# Sheet2.net
KiCad netlist of a schematic drawn in Altium Designer
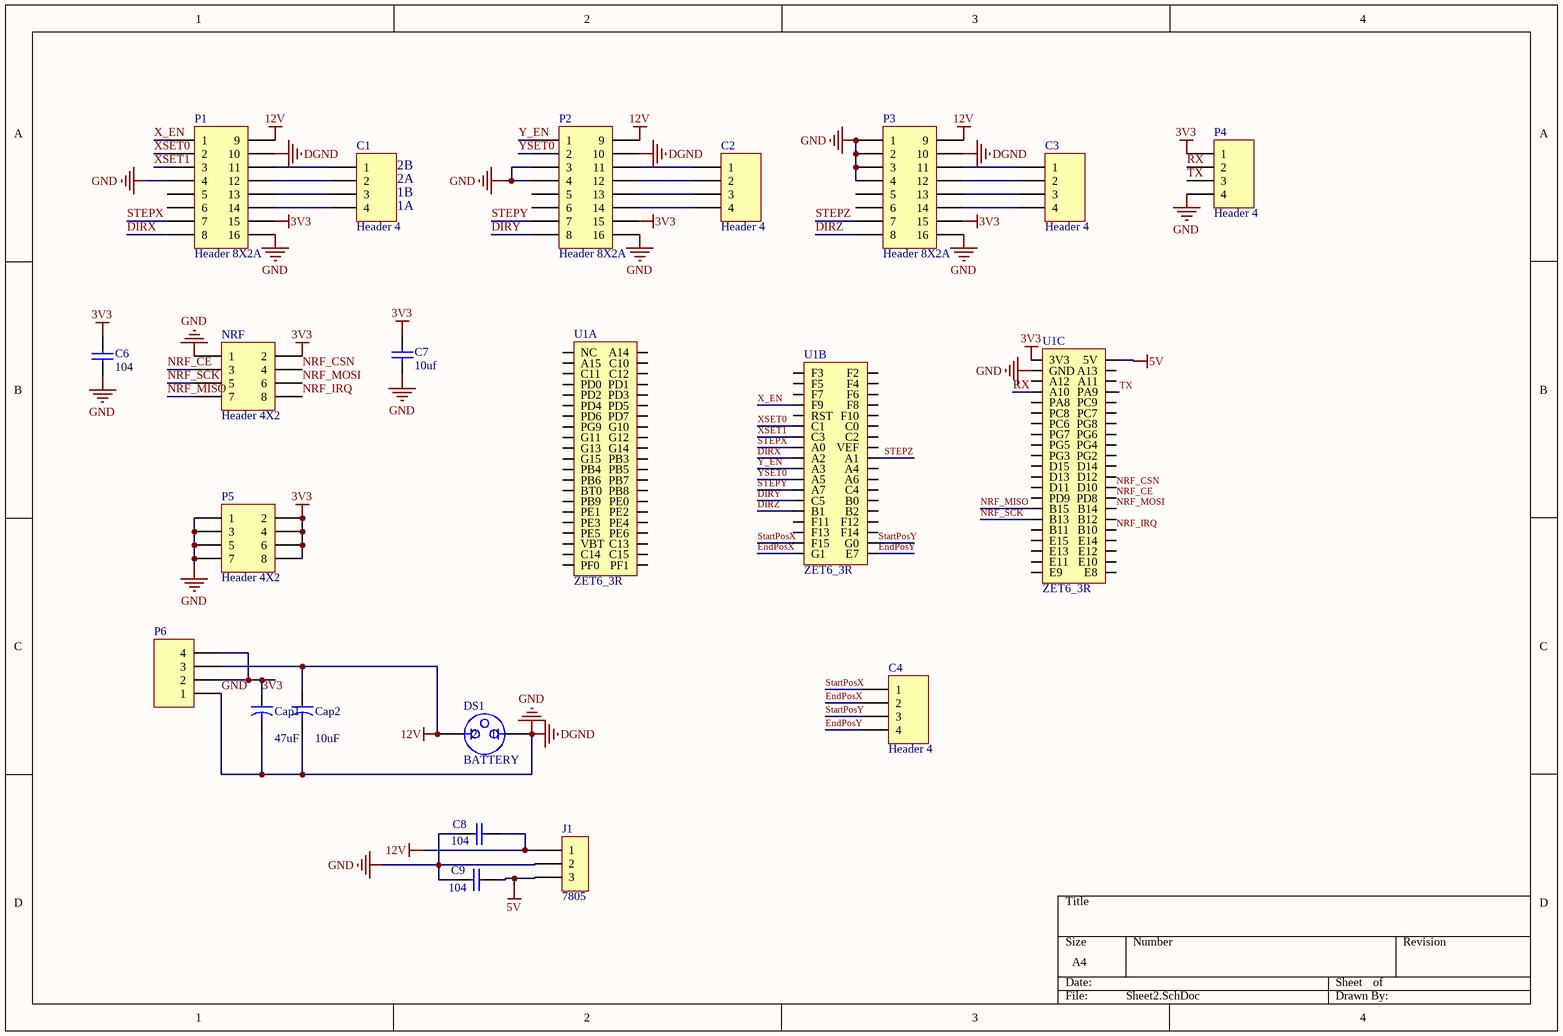
[diagram p0: Sheet2.SchDoc]

(export (version "E")
  (design (tool "Eeschema 10.0.6"))
  (components
    (comp (ref "C1")
      (value "Header 4")
      (footprint "HDR1X4")
      (description "Header, 4-Pin")
      (fields (field (name "PUBLISHER") "Altium Limited"))
      (libsource (lib "Miscellaneous Connectors") (part "Header 4"))
    )
    (comp (ref "C2")
      (value "Header 4")
      (footprint "HDR1X4")
      (description "Header, 4-Pin")
      (fields (field (name "PUBLISHER") "Altium Limited"))
      (libsource (lib "Miscellaneous Connectors") (part "Header 4"))
    )
    (comp (ref "C3")
      (value "Header 4")
      (footprint "HDR1X4")
      (description "Header, 4-Pin")
      (fields (field (name "PUBLISHER") "Altium Limited"))
      (libsource (lib "Miscellaneous Connectors") (part "Header 4"))
    )
    (comp (ref "C4")
      (value "Header 4")
      (footprint "HDR1X4")
      (description "Header, 4-Pin")
      (fields (field (name "PUBLISHER") "Altium Limited"))
      (libsource (lib "Miscellaneous Connectors") (part "Header 4"))
    )
    (comp (ref "C6")
      (value "104")
      (footprint "0805_C")
      (description "Capacitor")
      (fields (field (name "Comment") "Cap") (field (name "PUBLISHER") "Altium Limited"))
      (libsource (lib "nucleo原理图库") (part "Cap"))
    )
    (comp (ref "C7")
      (value "10uf")
      (footprint "10UF")
      (description "Capacitor")
      (fields (field (name "Comment") "Cap") (field (name "PUBLISHER") "Altium Limited"))
      (libsource (lib "nucleo原理图库") (part "Cap"))
    )
    (comp (ref "C8")
      (value "104")
      (footprint "0805_C")
      (description "Capacitor")
      (fields (field (name "Comment") "Cap") (field (name "PUBLISHER") "Altium Limited"))
      (libsource (lib "nucleo原理图库") (part "Cap"))
    )
    (comp (ref "C9")
      (value "104")
      (footprint "0805_C")
      (description "Capacitor")
      (fields (field (name "Comment") "Cap") (field (name "PUBLISHER") "Altium Limited"))
      (libsource (lib "nucleo原理图库") (part "Cap"))
    )
    (comp (ref "Cap1")
      (value "47uF")
      (footprint "CAPR5-4X5")
      (description "Capacitor")
      (fields (field (name "Comment") "Cap2") (field (name "PUBLISHER") "Altium Limited"))
      (libsource (lib "Miscellaneous Devices") (part "Cap2"))
    )
    (comp (ref "Cap2")
      (value "10uF")
      (footprint "CAPR5-4X5")
      (description "Capacitor")
      (fields (field (name "Comment") "Cap2") (field (name "PUBLISHER") "Altium Limited"))
      (libsource (lib "Miscellaneous Devices") (part "Cap2"))
    )
    (comp (ref "DS1") (value "BATTERY") (footprint "9V") (libsource (lib "nucleo原理图库") (part "BATTERY")))
    (comp (ref "J1")
      (value "7805")
      (footprint "TO-220")
      (description "Connector")
      (libsource (lib "杂元件库") (part "CON3"))
    )
    (comp (ref "NRF")
      (value "Header 4X2")
      (footprint "nucleo底板PCB库:HDR2X4")
      (description "Header, 4-Pin, Dual row")
      (fields (field (name "PUBLISHER") "Altium Limited"))
      (libsource (lib "Miscellaneous Connectors") (part "Header 4X2"))
    )
    (comp (ref "P1")
      (value "Header 8X2A")
      (footprint "PCBComponent_1")
      (description "Header, 8-Pin, Dual row")
      (fields (field (name "PUBLISHER") "Altium Limited"))
      (libsource (lib "Miscellaneous Connectors") (part "Header 8X2A"))
    )
    (comp (ref "P2")
      (value "Header 8X2A")
      (footprint "PCBComponent_1")
      (description "Header, 8-Pin, Dual row")
      (fields (field (name "PUBLISHER") "Altium Limited"))
      (libsource (lib "Miscellaneous Connectors") (part "Header 8X2A"))
    )
    (comp (ref "P3")
      (value "Header 8X2A")
      (footprint "PCBComponent_1")
      (description "Header, 8-Pin, Dual row")
      (fields (field (name "PUBLISHER") "Altium Limited"))
      (libsource (lib "Miscellaneous Connectors") (part "Header 8X2A"))
    )
    (comp (ref "P4")
      (value "Header 4")
      (footprint "HDR1X4")
      (description "Header, 4-Pin")
      (fields (field (name "PUBLISHER") "Altium Limited"))
      (libsource (lib "Miscellaneous Connectors") (part "Header 4"))
    )
    (comp (ref "P5")
      (value "Header 4X2")
      (footprint "HDR2X4")
      (description "Header, 4-Pin, Dual row")
      (fields (field (name "PUBLISHER") "Altium Limited"))
      (libsource (lib "Miscellaneous Connectors") (part "Header 4X2"))
    )
    (comp (ref "P6")
      (value "Header 4")
      (footprint "SOT-223")
      (description "Header, 4-Pin")
      (fields (field (name "PUBLISHER") "Altium Limited"))
      (libsource (lib "") (part "Header 4_1"))
    )
    (comp (ref "U1") (value "ZET6_3R") (footprint "PCBComponent_1") (libsource (lib "") (part "ZET6_3R_1")))
  )
  (nets
    (net (code "1") (name "/DIRX") (class "Default")
      (node (ref "P1") (pin "8") (pinfunction "8_8") (pintype "passive"))
      (node (ref "U1") (pin "60") (pinfunction "A2_60") (pintype "passive"))
    )
    (net (code "2") (name "/DIRY") (class "Default")
      (node (ref "P2") (pin "8") (pinfunction "8_8") (pintype "passive"))
      (node (ref "U1") (pin "68") (pinfunction "C5_68") (pintype "passive"))
    )
    (net (code "3") (name "/DIRZ") (class "Default")
      (node (ref "P3") (pin "8") (pinfunction "8_8") (pintype "passive"))
      (node (ref "U1") (pin "70") (pinfunction "B1_70") (pintype "passive"))
    )
    (net (code "4") (name "/EndPosX") (class "Default")
      (node (ref "C4") (pin "2") (pinfunction "2_2") (pintype "passive"))
      (node (ref "U1") (pin "78") (pinfunction "G1_78") (pintype "passive"))
    )
    (net (code "5") (name "/EndPosY") (class "Default")
      (node (ref "C4") (pin "4") (pinfunction "4_4") (pintype "passive"))
      (node (ref "U1") (pin "77") (pinfunction "E7_77") (pintype "passive"))
    )
    (net (code "6") (name "/NRF_CE") (class "Default")
      (node (ref "NRF") (pin "3") (pinfunction "3_3") (pintype "passive"))
      (node (ref "U1") (pin "93") (pinfunction "PD8_93") (pintype "passive"))
    )
    (net (code "7") (name "/NRF_CSN") (class "Default")
      (node (ref "NRF") (pin "4") (pinfunction "4_4") (pintype "passive"))
      (node (ref "U1") (pin "95") (pinfunction "D10_95") (pintype "passive"))
    )
    (net (code "8") (name "/NRF_IRQ") (class "Default")
      (node (ref "NRF") (pin "8") (pinfunction "8_8") (pintype "passive"))
      (node (ref "U1") (pin "87") (pinfunction "B10_87") (pintype "passive"))
    )
    (net (code "9") (name "/NRF_MISO") (class "Default")
      (node (ref "NRF") (pin "7") (pinfunction "7_7") (pintype "passive"))
      (node (ref "U1") (pin "92") (pinfunction "B15_92") (pintype "passive"))
    )
    (net (code "10") (name "/NRF_MOSI") (class "Default")
      (node (ref "NRF") (pin "6") (pinfunction "6_6") (pintype "passive"))
      (node (ref "U1") (pin "91") (pinfunction "B14_91") (pintype "passive"))
    )
    (net (code "11") (name "/NRF_SCK") (class "Default")
      (node (ref "NRF") (pin "5") (pinfunction "5_5") (pintype "passive"))
      (node (ref "U1") (pin "90") (pinfunction "B13_90") (pintype "passive"))
    )
    (net (code "12") (name "/RX") (class "Default")
      (node (ref "P4") (pin "2") (pinfunction "2_2") (pintype "passive"))
      (node (ref "U1") (pin "114") (pinfunction "A10_114") (pintype "passive"))
    )
    (net (code "13") (name "/STEPX") (class "Default")
      (node (ref "P1") (pin "7") (pinfunction "7_7") (pintype "passive"))
      (node (ref "U1") (pin "58") (pinfunction "A0_58") (pintype "passive"))
    )
    (net (code "14") (name "/STEPY") (class "Default")
      (node (ref "P2") (pin "7") (pinfunction "7_7") (pintype "passive"))
      (node (ref "U1") (pin "66") (pinfunction "A7_66") (pintype "passive"))
    )
    (net (code "15") (name "/STEPZ") (class "Default")
      (node (ref "P3") (pin "7") (pinfunction "7_7") (pintype "passive"))
      (node (ref "U1") (pin "59") (pinfunction "A1_59") (pintype "passive"))
    )
    (net (code "16") (name "/StartPosX") (class "Default")
      (node (ref "C4") (pin "1") (pinfunction "1_1") (pintype "passive"))
      (node (ref "U1") (pin "76") (pinfunction "F15_76") (pintype "passive"))
    )
    (net (code "17") (name "/StartPosY") (class "Default")
      (node (ref "C4") (pin "3") (pinfunction "3_3") (pintype "passive"))
      (node (ref "U1") (pin "75") (pinfunction "G0_75") (pintype "passive"))
    )
    (net (code "18") (name "/TX") (class "Default")
      (node (ref "P4") (pin "3") (pinfunction "3_3") (pintype "passive"))
      (node (ref "U1") (pin "113") (pinfunction "PA9_113") (pintype "passive"))
    )
    (net (code "19") (name "/XSET0") (class "Default")
      (node (ref "P1") (pin "2") (pinfunction "2_2") (pintype "passive"))
      (node (ref "U1") (pin "54") (pinfunction "C1_54") (pintype "passive"))
    )
    (net (code "20") (name "/XSET1") (class "Default")
      (node (ref "P1") (pin "3") (pinfunction "3_3") (pintype "passive"))
      (node (ref "U1") (pin "56") (pinfunction "C3_56") (pintype "passive"))
    )
    (net (code "21") (name "/X_EN") (class "Default")
      (node (ref "P1") (pin "1") (pinfunction "1_1") (pintype "passive"))
      (node (ref "U1") (pin "50") (pinfunction "F9_50") (pintype "passive"))
    )
    (net (code "22") (name "/YSET0") (class "Default")
      (node (ref "P2") (pin "2") (pinfunction "2_2") (pintype "passive"))
      (node (ref "U1") (pin "64") (pinfunction "A5_64") (pintype "passive"))
    )
    (net (code "23") (name "/Y_EN") (class "Default")
      (node (ref "P2") (pin "1") (pinfunction "1_1") (pintype "passive"))
      (node (ref "U1") (pin "62") (pinfunction "A3_62") (pintype "passive"))
    )
    (net (code "24") (name "3V3") (class "Default")
      (node (ref "C6") (pin "1") (pinfunction "1_1") (pintype "passive"))
      (node (ref "C7") (pin "1") (pinfunction "1_1") (pintype "passive"))
      (node (ref "Cap1") (pin "1") (pinfunction "1_1") (pintype "passive"))
      (node (ref "NRF") (pin "2") (pinfunction "2_2") (pintype "passive"))
      (node (ref "P1") (pin "15") (pinfunction "15_15") (pintype "passive"))
      (node (ref "P2") (pin "15") (pinfunction "15_15") (pintype "passive"))
      (node (ref "P3") (pin "15") (pinfunction "15_15") (pintype "passive"))
      (node (ref "P4") (pin "1") (pinfunction "1_1") (pintype "passive"))
      (node (ref "P5") (pin "2") (pinfunction "2_2") (pintype "passive"))
      (node (ref "P5") (pin "4") (pinfunction "4_4") (pintype "passive"))
      (node (ref "P5") (pin "6") (pinfunction "6_6") (pintype "passive"))
      (node (ref "P5") (pin "8") (pinfunction "8_8") (pintype "passive"))
      (node (ref "P6") (pin "2") (pinfunction "2_2") (pintype "passive"))
      (node (ref "P6") (pin "4") (pinfunction "4_4") (pintype "passive"))
      (node (ref "U1") (pin "120") (pinfunction "3V3_120") (pintype "passive"))
    )
    (net (code "25") (name "5V") (class "Default")
      (node (ref "C9") (pin "1") (pinfunction "1_1") (pintype "passive"))
      (node (ref "J1") (pin "3") (pinfunction "3_3") (pintype "passive"))
      (node (ref "U1") (pin "119") (pinfunction "5V_119") (pintype "passive"))
    )
    (net (code "26") (name "12V") (class "Default")
      (node (ref "C8") (pin "2") (pinfunction "2_2") (pintype "passive"))
      (node (ref "Cap2") (pin "1") (pinfunction "1_1") (pintype "passive"))
      (node (ref "DS1") (pin "2") (pinfunction "2_2") (pintype "passive"))
      (node (ref "J1") (pin "1") (pinfunction "1_1") (pintype "passive"))
      (node (ref "P1") (pin "9") (pinfunction "9_9") (pintype "passive"))
      (node (ref "P2") (pin "9") (pinfunction "9_9") (pintype "passive"))
      (node (ref "P3") (pin "9") (pinfunction "9_9") (pintype "passive"))
      (node (ref "P6") (pin "3") (pinfunction "3_3") (pintype "passive"))
    )
    (net (code "27") (name "DGND") (class "Default")
      (node (ref "C6") (pin "2") (pinfunction "2_2") (pintype "passive"))
      (node (ref "C7") (pin "2") (pinfunction "2_2") (pintype "passive"))
      (node (ref "C8") (pin "1") (pinfunction "1_1") (pintype "passive"))
      (node (ref "C9") (pin "2") (pinfunction "2_2") (pintype "passive"))
      (node (ref "Cap1") (pin "2") (pinfunction "2_2") (pintype "passive"))
      (node (ref "Cap2") (pin "2") (pinfunction "2_2") (pintype "passive"))
      (node (ref "DS1") (pin "1") (pinfunction "1_1") (pintype "passive"))
      (node (ref "J1") (pin "2") (pinfunction "2_2") (pintype "passive"))
      (node (ref "NRF") (pin "1") (pinfunction "1_1") (pintype "passive"))
      (node (ref "P1") (pin "10") (pinfunction "10_10") (pintype "passive"))
      (node (ref "P1") (pin "16") (pinfunction "16_16") (pintype "passive"))
      (node (ref "P1") (pin "4") (pinfunction "4_4") (pintype "passive"))
      (node (ref "P2") (pin "10") (pinfunction "10_10") (pintype "passive"))
      (node (ref "P2") (pin "16") (pinfunction "16_16") (pintype "passive"))
      (node (ref "P2") (pin "3") (pinfunction "3_3") (pintype "passive"))
      (node (ref "P2") (pin "4") (pinfunction "4_4") (pintype "passive"))
      (node (ref "P3") (pin "1") (pinfunction "1_1") (pintype "passive"))
      (node (ref "P3") (pin "10") (pinfunction "10_10") (pintype "passive"))
      (node (ref "P3") (pin "16") (pinfunction "16_16") (pintype "passive"))
      (node (ref "P3") (pin "2") (pinfunction "2_2") (pintype "passive"))
      (node (ref "P3") (pin "3") (pinfunction "3_3") (pintype "passive"))
      (node (ref "P3") (pin "4") (pinfunction "4_4") (pintype "passive"))
      (node (ref "P4") (pin "4") (pinfunction "4_4") (pintype "passive"))
      (node (ref "P5") (pin "1") (pinfunction "1_1") (pintype "passive"))
      (node (ref "P5") (pin "3") (pinfunction "3_3") (pintype "passive"))
      (node (ref "P5") (pin "5") (pinfunction "5_5") (pintype "passive"))
      (node (ref "P5") (pin "7") (pinfunction "7_7") (pintype "passive"))
      (node (ref "P6") (pin "1") (pinfunction "1_1") (pintype "passive"))
      (node (ref "U1") (pin "118") (pinfunction "GND_118") (pintype "passive"))
    )
    (net (code "28") (name "Net-(C1-Pad1)") (class "Default")
      (node (ref "C1") (pin "1") (pinfunction "1_1") (pintype "passive"))
      (node (ref "P1") (pin "11") (pinfunction "11_11") (pintype "passive"))
    )
    (net (code "29") (name "Net-(C1-Pad2)") (class "Default")
      (node (ref "C1") (pin "2") (pinfunction "2_2") (pintype "passive"))
      (node (ref "P1") (pin "12") (pinfunction "12_12") (pintype "passive"))
    )
    (net (code "30") (name "Net-(C1-Pad3)") (class "Default")
      (node (ref "C1") (pin "3") (pinfunction "3_3") (pintype "passive"))
      (node (ref "P1") (pin "13") (pinfunction "13_13") (pintype "passive"))
    )
    (net (code "31") (name "Net-(C1-Pad4)") (class "Default")
      (node (ref "C1") (pin "4") (pinfunction "4_4") (pintype "passive"))
      (node (ref "P1") (pin "14") (pinfunction "14_14") (pintype "passive"))
    )
    (net (code "32") (name "Net-(C2-Pad1)") (class "Default")
      (node (ref "C2") (pin "1") (pinfunction "1_1") (pintype "passive"))
      (node (ref "P2") (pin "11") (pinfunction "11_11") (pintype "passive"))
    )
    (net (code "33") (name "Net-(C2-Pad2)") (class "Default")
      (node (ref "C2") (pin "2") (pinfunction "2_2") (pintype "passive"))
      (node (ref "P2") (pin "12") (pinfunction "12_12") (pintype "passive"))
    )
    (net (code "34") (name "Net-(C2-Pad3)") (class "Default")
      (node (ref "C2") (pin "3") (pinfunction "3_3") (pintype "passive"))
      (node (ref "P2") (pin "13") (pinfunction "13_13") (pintype "passive"))
    )
    (net (code "35") (name "Net-(C2-Pad4)") (class "Default")
      (node (ref "C2") (pin "4") (pinfunction "4_4") (pintype "passive"))
      (node (ref "P2") (pin "14") (pinfunction "14_14") (pintype "passive"))
    )
    (net (code "36") (name "Net-(C3-Pad1)") (class "Default")
      (node (ref "C3") (pin "1") (pinfunction "1_1") (pintype "passive"))
      (node (ref "P3") (pin "11") (pinfunction "11_11") (pintype "passive"))
    )
    (net (code "37") (name "Net-(C3-Pad2)") (class "Default")
      (node (ref "C3") (pin "2") (pinfunction "2_2") (pintype "passive"))
      (node (ref "P3") (pin "12") (pinfunction "12_12") (pintype "passive"))
    )
    (net (code "38") (name "Net-(C3-Pad3)") (class "Default")
      (node (ref "C3") (pin "3") (pinfunction "3_3") (pintype "passive"))
      (node (ref "P3") (pin "13") (pinfunction "13_13") (pintype "passive"))
    )
    (net (code "39") (name "Net-(C3-Pad4)") (class "Default")
      (node (ref "C3") (pin "4") (pinfunction "4_4") (pintype "passive"))
      (node (ref "P3") (pin "14") (pinfunction "14_14") (pintype "passive"))
    )
    (net (code "40") (name "unconnected-(P1-Pad5)") (class "Default")
      (node (ref "P1") (pin "5") (pinfunction "5_5") (pintype "passive"))
    )
    (net (code "41") (name "unconnected-(P1-Pad6)") (class "Default")
      (node (ref "P1") (pin "6") (pinfunction "6_6") (pintype "passive"))
    )
    (net (code "42") (name "unconnected-(P2-Pad5)") (class "Default")
      (node (ref "P2") (pin "5") (pinfunction "5_5") (pintype "passive"))
    )
    (net (code "43") (name "unconnected-(P2-Pad6)") (class "Default")
      (node (ref "P2") (pin "6") (pinfunction "6_6") (pintype "passive"))
    )
    (net (code "44") (name "unconnected-(P3-Pad5)") (class "Default")
      (node (ref "P3") (pin "5") (pinfunction "5_5") (pintype "passive"))
    )
    (net (code "45") (name "unconnected-(P3-Pad6)") (class "Default")
      (node (ref "P3") (pin "6") (pinfunction "6_6") (pintype "passive"))
    )
    (net (code "46") (name "unconnected-(U1A-A14-Pad2)") (class "Default")
      (node (ref "U1") (pin "2") (pinfunction "A14_2") (pintype "passive"))
    )
    (net (code "47") (name "unconnected-(U1A-A15-Pad3)") (class "Default")
      (node (ref "U1") (pin "3") (pinfunction "A15_3") (pintype "passive"))
    )
    (net (code "48") (name "unconnected-(U1A-BT0-Pad27)") (class "Default")
      (node (ref "U1") (pin "27") (pinfunction "BT0_27") (pintype "passive"))
    )
    (net (code "49") (name "unconnected-(U1A-C10-Pad4)") (class "Default")
      (node (ref "U1") (pin "4") (pinfunction "C10_4") (pintype "passive"))
    )
    (net (code "50") (name "unconnected-(U1A-C11-Pad5)") (class "Default")
      (node (ref "U1") (pin "5") (pinfunction "C11_5") (pintype "passive"))
    )
    (net (code "51") (name "unconnected-(U1A-C12-Pad6)") (class "Default")
      (node (ref "U1") (pin "6") (pinfunction "C12_6") (pintype "passive"))
    )
    (net (code "52") (name "unconnected-(U1A-C13-Pad38)") (class "Default")
      (node (ref "U1") (pin "38") (pinfunction "C13_38") (pintype "passive"))
    )
    (net (code "53") (name "unconnected-(U1A-C14-Pad39)") (class "Default")
      (node (ref "U1") (pin "39") (pinfunction "C14_39") (pintype "passive"))
    )
    (net (code "54") (name "unconnected-(U1A-C15-Pad40)") (class "Default")
      (node (ref "U1") (pin "40") (pinfunction "C15_40") (pintype "passive"))
    )
    (net (code "55") (name "unconnected-(U1A-G10-Pad16)") (class "Default")
      (node (ref "U1") (pin "16") (pinfunction "G10_16") (pintype "passive"))
    )
    (net (code "56") (name "unconnected-(U1A-G11-Pad17)") (class "Default")
      (node (ref "U1") (pin "17") (pinfunction "G11_17") (pintype "passive"))
    )
    (net (code "57") (name "unconnected-(U1A-G12-Pad18)") (class "Default")
      (node (ref "U1") (pin "18") (pinfunction "G12_18") (pintype "passive"))
    )
    (net (code "58") (name "unconnected-(U1A-G13-Pad19)") (class "Default")
      (node (ref "U1") (pin "19") (pinfunction "G13_19") (pintype "passive"))
    )
    (net (code "59") (name "unconnected-(U1A-G14-Pad20)") (class "Default")
      (node (ref "U1") (pin "20") (pinfunction "G14_20") (pintype "passive"))
    )
    (net (code "60") (name "unconnected-(U1A-G15-Pad21)") (class "Default")
      (node (ref "U1") (pin "21") (pinfunction "G15_21") (pintype "passive"))
    )
    (net (code "61") (name "unconnected-(U1A-NC-Pad1)") (class "Default")
      (node (ref "U1") (pin "1") (pinfunction "NC_1") (pintype "passive"))
    )
    (net (code "62") (name "unconnected-(U1A-PB3-Pad22)") (class "Default")
      (node (ref "U1") (pin "22") (pinfunction "PB3_22") (pintype "passive"))
    )
    (net (code "63") (name "unconnected-(U1A-PB4-Pad23)") (class "Default")
      (node (ref "U1") (pin "23") (pinfunction "PB4_23") (pintype "passive"))
    )
    (net (code "64") (name "unconnected-(U1A-PB5-Pad24)") (class "Default")
      (node (ref "U1") (pin "24") (pinfunction "PB5_24") (pintype "passive"))
    )
    (net (code "65") (name "unconnected-(U1A-PB6-Pad25)") (class "Default")
      (node (ref "U1") (pin "25") (pinfunction "PB6_25") (pintype "passive"))
    )
    (net (code "66") (name "unconnected-(U1A-PB7-Pad26)") (class "Default")
      (node (ref "U1") (pin "26") (pinfunction "PB7_26") (pintype "passive"))
    )
    (net (code "67") (name "unconnected-(U1A-PB8-Pad28)") (class "Default")
      (node (ref "U1") (pin "28") (pinfunction "PB8_28") (pintype "passive"))
    )
    (net (code "68") (name "unconnected-(U1A-PB9-Pad29)") (class "Default")
      (node (ref "U1") (pin "29") (pinfunction "PB9_29") (pintype "passive"))
    )
    (net (code "69") (name "unconnected-(U1A-PD0-Pad7)") (class "Default")
      (node (ref "U1") (pin "7") (pinfunction "PD0_7") (pintype "passive"))
    )
    (net (code "70") (name "unconnected-(U1A-PD1-Pad8)") (class "Default")
      (node (ref "U1") (pin "8") (pinfunction "PD1_8") (pintype "passive"))
    )
    (net (code "71") (name "unconnected-(U1A-PD2-Pad9)") (class "Default")
      (node (ref "U1") (pin "9") (pinfunction "PD2_9") (pintype "passive"))
    )
    (net (code "72") (name "unconnected-(U1A-PD3-Pad10)") (class "Default")
      (node (ref "U1") (pin "10") (pinfunction "PD3_10") (pintype "passive"))
    )
    (net (code "73") (name "unconnected-(U1A-PD4-Pad11)") (class "Default")
      (node (ref "U1") (pin "11") (pinfunction "PD4_11") (pintype "passive"))
    )
    (net (code "74") (name "unconnected-(U1A-PD5-Pad12)") (class "Default")
      (node (ref "U1") (pin "12") (pinfunction "PD5_12") (pintype "passive"))
    )
    (net (code "75") (name "unconnected-(U1A-PD6-Pad13)") (class "Default")
      (node (ref "U1") (pin "13") (pinfunction "PD6_13") (pintype "passive"))
    )
    (net (code "76") (name "unconnected-(U1A-PD7-Pad14)") (class "Default")
      (node (ref "U1") (pin "14") (pinfunction "PD7_14") (pintype "passive"))
    )
    (net (code "77") (name "unconnected-(U1A-PE0-Pad30)") (class "Default")
      (node (ref "U1") (pin "30") (pinfunction "PE0_30") (pintype "passive"))
    )
    (net (code "78") (name "unconnected-(U1A-PE1-Pad31)") (class "Default")
      (node (ref "U1") (pin "31") (pinfunction "PE1_31") (pintype "passive"))
    )
    (net (code "79") (name "unconnected-(U1A-PE2-Pad32)") (class "Default")
      (node (ref "U1") (pin "32") (pinfunction "PE2_32") (pintype "passive"))
    )
    (net (code "80") (name "unconnected-(U1A-PE3-Pad33)") (class "Default")
      (node (ref "U1") (pin "33") (pinfunction "PE3_33") (pintype "passive"))
    )
    (net (code "81") (name "unconnected-(U1A-PE4-Pad34)") (class "Default")
      (node (ref "U1") (pin "34") (pinfunction "PE4_34") (pintype "passive"))
    )
    (net (code "82") (name "unconnected-(U1A-PE5-Pad35)") (class "Default")
      (node (ref "U1") (pin "35") (pinfunction "PE5_35") (pintype "passive"))
    )
    (net (code "83") (name "unconnected-(U1A-PE6-Pad36)") (class "Default")
      (node (ref "U1") (pin "36") (pinfunction "PE6_36") (pintype "passive"))
    )
    (net (code "84") (name "unconnected-(U1A-PF0-Pad41)") (class "Default")
      (node (ref "U1") (pin "41") (pinfunction "PF0_41") (pintype "passive"))
    )
    (net (code "85") (name "unconnected-(U1A-PF1-Pad42)") (class "Default")
      (node (ref "U1") (pin "42") (pinfunction "PF1_42") (pintype "passive"))
    )
    (net (code "86") (name "unconnected-(U1A-PG9-Pad15)") (class "Default")
      (node (ref "U1") (pin "15") (pinfunction "PG9_15") (pintype "passive"))
    )
    (net (code "87") (name "unconnected-(U1A-VBT-Pad37)") (class "Default")
      (node (ref "U1") (pin "37") (pinfunction "VBT_37") (pintype "passive"))
    )
    (net (code "88") (name "unconnected-(U1B-A4-Pad61)") (class "Default")
      (node (ref "U1") (pin "61") (pinfunction "A4_61") (pintype "passive"))
    )
    (net (code "89") (name "unconnected-(U1B-A6-Pad63)") (class "Default")
      (node (ref "U1") (pin "63") (pinfunction "A6_63") (pintype "passive"))
    )
    (net (code "90") (name "unconnected-(U1B-B0-Pad67)") (class "Default")
      (node (ref "U1") (pin "67") (pinfunction "B0_67") (pintype "passive"))
    )
    (net (code "91") (name "unconnected-(U1B-B2-Pad69)") (class "Default")
      (node (ref "U1") (pin "69") (pinfunction "B2_69") (pintype "passive"))
    )
    (net (code "92") (name "unconnected-(U1B-C0-Pad53)") (class "Default")
      (node (ref "U1") (pin "53") (pinfunction "C0_53") (pintype "passive"))
    )
    (net (code "93") (name "unconnected-(U1B-C2-Pad55)") (class "Default")
      (node (ref "U1") (pin "55") (pinfunction "C2_55") (pintype "passive"))
    )
    (net (code "94") (name "unconnected-(U1B-C4-Pad65)") (class "Default")
      (node (ref "U1") (pin "65") (pinfunction "C4_65") (pintype "passive"))
    )
    (net (code "95") (name "unconnected-(U1B-F2-Pad43)") (class "Default")
      (node (ref "U1") (pin "43") (pinfunction "F2_43") (pintype "passive"))
    )
    (net (code "96") (name "unconnected-(U1B-F3-Pad44)") (class "Default")
      (node (ref "U1") (pin "44") (pinfunction "F3_44") (pintype "passive"))
    )
    (net (code "97") (name "unconnected-(U1B-F4-Pad45)") (class "Default")
      (node (ref "U1") (pin "45") (pinfunction "F4_45") (pintype "passive"))
    )
    (net (code "98") (name "unconnected-(U1B-F5-Pad46)") (class "Default")
      (node (ref "U1") (pin "46") (pinfunction "F5_46") (pintype "passive"))
    )
    (net (code "99") (name "unconnected-(U1B-F6-Pad47)") (class "Default")
      (node (ref "U1") (pin "47") (pinfunction "F6_47") (pintype "passive"))
    )
    (net (code "100") (name "unconnected-(U1B-F7-Pad48)") (class "Default")
      (node (ref "U1") (pin "48") (pinfunction "F7_48") (pintype "passive"))
    )
    (net (code "101") (name "unconnected-(U1B-F8-Pad49)") (class "Default")
      (node (ref "U1") (pin "49") (pinfunction "F8_49") (pintype "passive"))
    )
    (net (code "102") (name "unconnected-(U1B-F10-Pad51)") (class "Default")
      (node (ref "U1") (pin "51") (pinfunction "F10_51") (pintype "passive"))
    )
    (net (code "103") (name "unconnected-(U1B-F11-Pad72)") (class "Default")
      (node (ref "U1") (pin "72") (pinfunction "F11_72") (pintype "passive"))
    )
    (net (code "104") (name "unconnected-(U1B-F12-Pad71)") (class "Default")
      (node (ref "U1") (pin "71") (pinfunction "F12_71") (pintype "passive"))
    )
    (net (code "105") (name "unconnected-(U1B-F13-Pad74)") (class "Default")
      (node (ref "U1") (pin "74") (pinfunction "F13_74") (pintype "passive"))
    )
    (net (code "106") (name "unconnected-(U1B-F14-Pad73)") (class "Default")
      (node (ref "U1") (pin "73") (pinfunction "F14_73") (pintype "passive"))
    )
    (net (code "107") (name "unconnected-(U1B-RST-Pad52)") (class "Default")
      (node (ref "U1") (pin "52") (pinfunction "RST_52") (pintype "passive"))
    )
    (net (code "108") (name "unconnected-(U1B-VEF-Pad57)") (class "Default")
      (node (ref "U1") (pin "57") (pinfunction "VEF_57") (pintype "passive"))
    )
    (net (code "109") (name "unconnected-(U1C-A11-Pad115)") (class "Default")
      (node (ref "U1") (pin "115") (pinfunction "A11_115") (pintype "passive"))
    )
    (net (code "110") (name "unconnected-(U1C-A12-Pad116)") (class "Default")
      (node (ref "U1") (pin "116") (pinfunction "A12_116") (pintype "passive"))
    )
    (net (code "111") (name "unconnected-(U1C-A13-Pad117)") (class "Default")
      (node (ref "U1") (pin "117") (pinfunction "A13_117") (pintype "passive"))
    )
    (net (code "112") (name "unconnected-(U1C-B11-Pad88)") (class "Default")
      (node (ref "U1") (pin "88") (pinfunction "B11_88") (pintype "passive"))
    )
    (net (code "113") (name "unconnected-(U1C-B12-Pad89)") (class "Default")
      (node (ref "U1") (pin "89") (pinfunction "B12_89") (pintype "passive"))
    )
    (net (code "114") (name "unconnected-(U1C-D11-Pad96)") (class "Default")
      (node (ref "U1") (pin "96") (pinfunction "D11_96") (pintype "passive"))
    )
    (net (code "115") (name "unconnected-(U1C-D12-Pad97)") (class "Default")
      (node (ref "U1") (pin "97") (pinfunction "D12_97") (pintype "passive"))
    )
    (net (code "116") (name "unconnected-(U1C-D13-Pad98)") (class "Default")
      (node (ref "U1") (pin "98") (pinfunction "D13_98") (pintype "passive"))
    )
    (net (code "117") (name "unconnected-(U1C-D14-Pad99)") (class "Default")
      (node (ref "U1") (pin "99") (pinfunction "D14_99") (pintype "passive"))
    )
    (net (code "118") (name "unconnected-(U1C-D15-Pad100)") (class "Default")
      (node (ref "U1") (pin "100") (pinfunction "D15_100") (pintype "passive"))
    )
    (net (code "119") (name "unconnected-(U1C-E8-Pad79)") (class "Default")
      (node (ref "U1") (pin "79") (pinfunction "E8_79") (pintype "passive"))
    )
    (net (code "120") (name "unconnected-(U1C-E9-Pad80)") (class "Default")
      (node (ref "U1") (pin "80") (pinfunction "E9_80") (pintype "passive"))
    )
    (net (code "121") (name "unconnected-(U1C-E10-Pad81)") (class "Default")
      (node (ref "U1") (pin "81") (pinfunction "E10_81") (pintype "passive"))
    )
    (net (code "122") (name "unconnected-(U1C-E11-Pad82)") (class "Default")
      (node (ref "U1") (pin "82") (pinfunction "E11_82") (pintype "passive"))
    )
    (net (code "123") (name "unconnected-(U1C-E12-Pad83)") (class "Default")
      (node (ref "U1") (pin "83") (pinfunction "E12_83") (pintype "passive"))
    )
    (net (code "124") (name "unconnected-(U1C-E13-Pad84)") (class "Default")
      (node (ref "U1") (pin "84") (pinfunction "E13_84") (pintype "passive"))
    )
    (net (code "125") (name "unconnected-(U1C-E14-Pad85)") (class "Default")
      (node (ref "U1") (pin "85") (pinfunction "E14_85") (pintype "passive"))
    )
    (net (code "126") (name "unconnected-(U1C-E15-Pad86)") (class "Default")
      (node (ref "U1") (pin "86") (pinfunction "E15_86") (pintype "passive"))
    )
    (net (code "127") (name "unconnected-(U1C-PA8-Pad112)") (class "Default")
      (node (ref "U1") (pin "112") (pinfunction "PA8_112") (pintype "passive"))
    )
    (net (code "128") (name "unconnected-(U1C-PC6-Pad108)") (class "Default")
      (node (ref "U1") (pin "108") (pinfunction "PC6_108") (pintype "passive"))
    )
    (net (code "129") (name "unconnected-(U1C-PC7-Pad109)") (class "Default")
      (node (ref "U1") (pin "109") (pinfunction "PC7_109") (pintype "passive"))
    )
    (net (code "130") (name "unconnected-(U1C-PC8-Pad110)") (class "Default")
      (node (ref "U1") (pin "110") (pinfunction "PC8_110") (pintype "passive"))
    )
    (net (code "131") (name "unconnected-(U1C-PC9-Pad111)") (class "Default")
      (node (ref "U1") (pin "111") (pinfunction "PC9_111") (pintype "passive"))
    )
    (net (code "132") (name "unconnected-(U1C-PD9-Pad94)") (class "Default")
      (node (ref "U1") (pin "94") (pinfunction "PD9_94") (pintype "passive"))
    )
    (net (code "133") (name "unconnected-(U1C-PG2-Pad101)") (class "Default")
      (node (ref "U1") (pin "101") (pinfunction "PG2_101") (pintype "passive"))
    )
    (net (code "134") (name "unconnected-(U1C-PG3-Pad102)") (class "Default")
      (node (ref "U1") (pin "102") (pinfunction "PG3_102") (pintype "passive"))
    )
    (net (code "135") (name "unconnected-(U1C-PG4-Pad103)") (class "Default")
      (node (ref "U1") (pin "103") (pinfunction "PG4_103") (pintype "passive"))
    )
    (net (code "136") (name "unconnected-(U1C-PG5-Pad104)") (class "Default")
      (node (ref "U1") (pin "104") (pinfunction "PG5_104") (pintype "passive"))
    )
    (net (code "137") (name "unconnected-(U1C-PG6-Pad105)") (class "Default")
      (node (ref "U1") (pin "105") (pinfunction "PG6_105") (pintype "passive"))
    )
    (net (code "138") (name "unconnected-(U1C-PG7-Pad106)") (class "Default")
      (node (ref "U1") (pin "106") (pinfunction "PG7_106") (pintype "passive"))
    )
    (net (code "139") (name "unconnected-(U1C-PG8-Pad107)") (class "Default")
      (node (ref "U1") (pin "107") (pinfunction "PG8_107") (pintype "passive"))
    )
  )
)
